# 03_-_CPU_POWER.net
KiCad netlist of a schematic drawn in Altium Designer
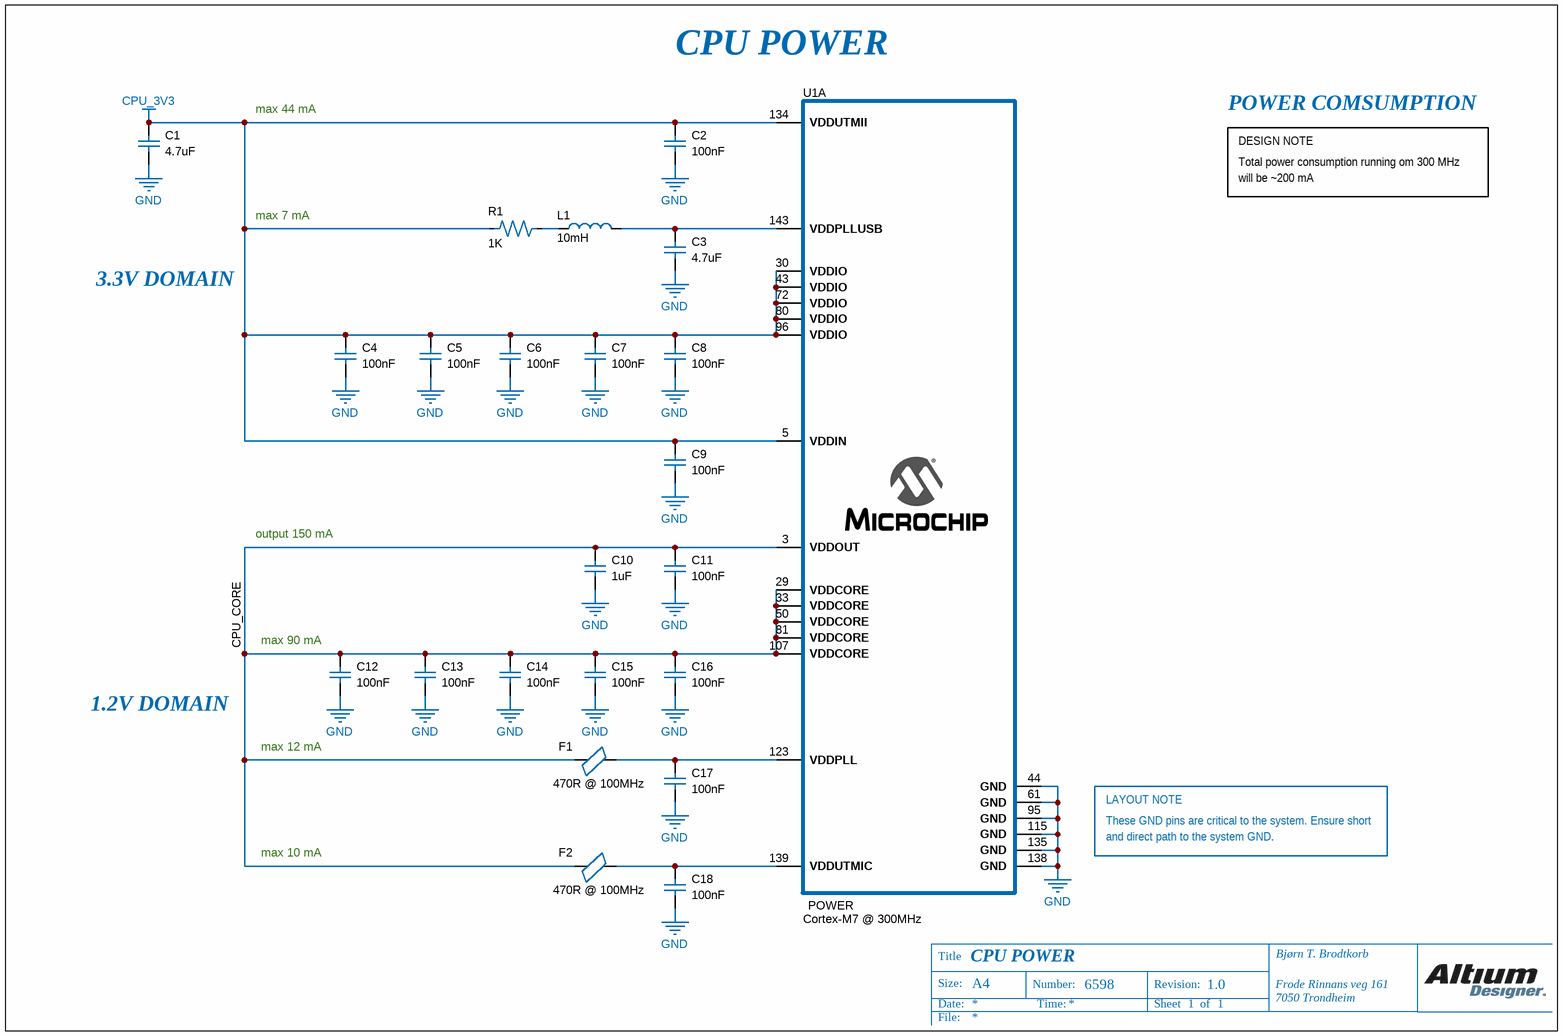
[diagram p0: [03] - CPU POWER.SchDoc]

(export (version "E")
  (design (tool "Eeschema 10.0.6"))
  (components
    (comp (ref "C1")
      (value "4.7uF")
      (footprint "C0603")
      (description "C0603")
      (fields (field (name "Comment") "02016D104KAT2A"))
      (libsource (lib "Passive components") (part "02016D104KAT2A"))
    )
    (comp (ref "C2")
      (value "100nF")
      (footprint "C0402")
      (description "C0402")
      (fields (field (name "Comment") "04023C103KAT2A"))
      (libsource (lib "Passive components") (part "04023C103KAT2A"))
    )
    (comp (ref "C3")
      (value "4.7uF")
      (footprint "C0402")
      (description "C0402")
      (fields (field (name "Comment") "04023C103KAT2A"))
      (libsource (lib "Passive components") (part "04023C103KAT2A"))
    )
    (comp (ref "C4")
      (value "100nF")
      (footprint "C0402")
      (description "C0402")
      (fields (field (name "Comment") "04023C103KAT2A"))
      (libsource (lib "Passive components") (part "04023C103KAT2A"))
    )
    (comp (ref "C5")
      (value "100nF")
      (footprint "C0402")
      (description "C0402")
      (fields (field (name "Comment") "04023C103KAT2A"))
      (libsource (lib "Passive components") (part "04023C103KAT2A"))
    )
    (comp (ref "C6")
      (value "100nF")
      (footprint "C0402")
      (description "C0402")
      (fields (field (name "Comment") "04023C103KAT2A"))
      (libsource (lib "Passive components") (part "04023C103KAT2A"))
    )
    (comp (ref "C7")
      (value "100nF")
      (footprint "C0402")
      (description "C0402")
      (fields (field (name "Comment") "04023C103KAT2A"))
      (libsource (lib "Passive components") (part "04023C103KAT2A"))
    )
    (comp (ref "C8")
      (value "100nF")
      (footprint "C0402")
      (description "C0402")
      (fields (field (name "Comment") "04023C103KAT2A"))
      (libsource (lib "Passive components") (part "04023C103KAT2A"))
    )
    (comp (ref "C9")
      (value "100nF")
      (footprint "C0402")
      (description "C0402")
      (fields (field (name "Comment") "04023C103KAT2A"))
      (libsource (lib "Passive components") (part "04023C103KAT2A"))
    )
    (comp (ref "C10")
      (value "1uF")
      (footprint "C0402")
      (description "C0402")
      (fields (field (name "Comment") "04023C103KAT2A"))
      (libsource (lib "Passive components") (part "04023C103KAT2A"))
    )
    (comp (ref "C11")
      (value "100nF")
      (footprint "C0402")
      (description "C0402")
      (fields (field (name "Comment") "04023C103KAT2A"))
      (libsource (lib "Passive components") (part "04023C103KAT2A"))
    )
    (comp (ref "C12")
      (value "100nF")
      (footprint "C0402")
      (description "C0402")
      (fields (field (name "Comment") "04023C103KAT2A"))
      (libsource (lib "Passive components") (part "04023C103KAT2A"))
    )
    (comp (ref "C13")
      (value "100nF")
      (footprint "C0402")
      (description "C0402")
      (fields (field (name "Comment") "04023C103KAT2A"))
      (libsource (lib "Passive components") (part "04023C103KAT2A"))
    )
    (comp (ref "C14")
      (value "100nF")
      (footprint "C0402")
      (description "C0402")
      (fields (field (name "Comment") "04023C103KAT2A"))
      (libsource (lib "Passive components") (part "04023C103KAT2A"))
    )
    (comp (ref "C15")
      (value "100nF")
      (footprint "C0402")
      (description "C0402")
      (fields (field (name "Comment") "04023C103KAT2A"))
      (libsource (lib "Passive components") (part "04023C103KAT2A"))
    )
    (comp (ref "C16")
      (value "100nF")
      (footprint "C0402")
      (description "C0402")
      (fields (field (name "Comment") "04023C103KAT2A"))
      (libsource (lib "Passive components") (part "04023C103KAT2A"))
    )
    (comp (ref "C17")
      (value "100nF")
      (footprint "C0402")
      (description "C0402")
      (fields (field (name "Comment") "04023C103KAT2A"))
      (libsource (lib "Passive components") (part "04023C103KAT2A"))
    )
    (comp (ref "C18")
      (value "100nF")
      (footprint "C0402")
      (description "C0402")
      (fields (field (name "Comment") "04023C103KAT2A"))
      (libsource (lib "Passive components") (part "04023C103KAT2A"))
    )
    (comp (ref "F1")
      (value "470R @ 100MHz")
      (footprint "Ferrite bead 0402")
      (description "Ferrite bead 0402")
      (fields (field (name "Comment") "BLM15AG102SN1D"))
      (libsource (lib "Passive components") (part "BLM15AG102SN1D"))
    )
    (comp (ref "F2")
      (value "470R @ 100MHz")
      (footprint "Ferrite bead 0402")
      (description "Ferrite bead 0402")
      (fields (field (name "Comment") "BLM15AG102SN1D"))
      (libsource (lib "Passive components") (part "BLM15AG102SN1D"))
    )
    (comp (ref "L1")
      (value "10mH")
      (footprint "Inductor 0603")
      (description "Inductor 0603")
      (fields (field (name "Comment") "MLZ1608A2R2WT"))
      (libsource (lib "Passive components") (part "MLZ1608A2R2WT"))
    )
    (comp (ref "R1")
      (value "1K")
      (footprint "R0402")
      (description "R0402")
      (fields (field (name "Comment") "CRCW04020000Z0ED"))
      (libsource (lib "Passive components") (part "CRCW04020000Z0ED"))
    )
    (comp (ref "U1")
      (value "Cortex-M7 @ 300MHz")
      (footprint "ATSAMS70Q21A-AN")
      (description "ATSAMS70Q21")
      (libsource (lib "Microcontrollers") (part "ATSAMS70Q21A-AN"))
    )
  )
  (nets
    (net (code "1") (name "/CPU_CORE") (class "Default")
      (node (ref "C10") (pin "2") (pinfunction "2_2") (pintype "passive"))
      (node (ref "C11") (pin "2") (pinfunction "2_2") (pintype "passive"))
      (node (ref "C12") (pin "2") (pinfunction "2_2") (pintype "passive"))
      (node (ref "C13") (pin "2") (pinfunction "2_2") (pintype "passive"))
      (node (ref "C14") (pin "2") (pinfunction "2_2") (pintype "passive"))
      (node (ref "C15") (pin "2") (pinfunction "2_2") (pintype "passive"))
      (node (ref "C16") (pin "2") (pinfunction "2_2") (pintype "passive"))
      (node (ref "F1") (pin "1") (pinfunction "1_1") (pintype "passive"))
      (node (ref "F2") (pin "1") (pinfunction "1_1") (pintype "passive"))
      (node (ref "U1") (pin "107") (pinfunction "VDDCORE_107") (pintype "power_in"))
      (node (ref "U1") (pin "29") (pinfunction "VDDCORE_29") (pintype "power_in"))
      (node (ref "U1") (pin "3") (pinfunction "VDDOUT_3") (pintype "power_in"))
      (node (ref "U1") (pin "33") (pinfunction "VDDCORE_33") (pintype "power_in"))
      (node (ref "U1") (pin "50") (pinfunction "VDDCORE_50") (pintype "power_in"))
      (node (ref "U1") (pin "81") (pinfunction "VDDCORE_81") (pintype "power_in"))
    )
    (net (code "2") (name "CPU_3V3") (class "Default")
      (node (ref "C1") (pin "1") (pinfunction "1_1") (pintype "passive"))
      (node (ref "C2") (pin "2") (pinfunction "2_2") (pintype "passive"))
      (node (ref "C4") (pin "2") (pinfunction "2_2") (pintype "passive"))
      (node (ref "C5") (pin "2") (pinfunction "2_2") (pintype "passive"))
      (node (ref "C6") (pin "2") (pinfunction "2_2") (pintype "passive"))
      (node (ref "C7") (pin "2") (pinfunction "2_2") (pintype "passive"))
      (node (ref "C8") (pin "2") (pinfunction "2_2") (pintype "passive"))
      (node (ref "C9") (pin "2") (pinfunction "2_2") (pintype "passive"))
      (node (ref "R1") (pin "1") (pinfunction "1_1") (pintype "passive"))
      (node (ref "U1") (pin "134") (pinfunction "VDDUTMII_134") (pintype "power_in"))
      (node (ref "U1") (pin "30") (pinfunction "VDDIO_30") (pintype "power_in"))
      (node (ref "U1") (pin "43") (pinfunction "VDDIO_43") (pintype "power_in"))
      (node (ref "U1") (pin "5") (pinfunction "VDDIN_5") (pintype "power_in"))
      (node (ref "U1") (pin "72") (pinfunction "VDDIO_72") (pintype "power_in"))
      (node (ref "U1") (pin "80") (pinfunction "VDDIO_80") (pintype "power_in"))
      (node (ref "U1") (pin "96") (pinfunction "VDDIO_96") (pintype "power_in"))
    )
    (net (code "3") (name "GND") (class "Default")
      (node (ref "C1") (pin "2") (pinfunction "2_2") (pintype "passive"))
      (node (ref "C10") (pin "1") (pinfunction "1_1") (pintype "passive"))
      (node (ref "C11") (pin "1") (pinfunction "1_1") (pintype "passive"))
      (node (ref "C12") (pin "1") (pinfunction "1_1") (pintype "passive"))
      (node (ref "C13") (pin "1") (pinfunction "1_1") (pintype "passive"))
      (node (ref "C14") (pin "1") (pinfunction "1_1") (pintype "passive"))
      (node (ref "C15") (pin "1") (pinfunction "1_1") (pintype "passive"))
      (node (ref "C16") (pin "1") (pinfunction "1_1") (pintype "passive"))
      (node (ref "C17") (pin "1") (pinfunction "1_1") (pintype "passive"))
      (node (ref "C18") (pin "1") (pinfunction "1_1") (pintype "passive"))
      (node (ref "C2") (pin "1") (pinfunction "1_1") (pintype "passive"))
      (node (ref "C3") (pin "1") (pinfunction "1_1") (pintype "passive"))
      (node (ref "C4") (pin "1") (pinfunction "1_1") (pintype "passive"))
      (node (ref "C5") (pin "1") (pinfunction "1_1") (pintype "passive"))
      (node (ref "C6") (pin "1") (pinfunction "1_1") (pintype "passive"))
      (node (ref "C7") (pin "1") (pinfunction "1_1") (pintype "passive"))
      (node (ref "C8") (pin "1") (pinfunction "1_1") (pintype "passive"))
      (node (ref "C9") (pin "1") (pinfunction "1_1") (pintype "passive"))
      (node (ref "U1") (pin "115") (pinfunction "GND_115") (pintype "power_in"))
      (node (ref "U1") (pin "135") (pinfunction "GND_135") (pintype "power_in"))
      (node (ref "U1") (pin "138") (pinfunction "GND_138") (pintype "power_in"))
      (node (ref "U1") (pin "44") (pinfunction "GND_44") (pintype "power_in"))
      (node (ref "U1") (pin "61") (pinfunction "GND_61") (pintype "power_in"))
      (node (ref "U1") (pin "95") (pinfunction "GND_95") (pintype "power_in"))
    )
    (net (code "4") (name "Net-(R1-3)") (class "Default")
      (node (ref "L1") (pin "1") (pinfunction "1_1") (pintype "passive"))
      (node (ref "R1") (pin "2") (pinfunction "3_2") (pintype "passive"))
    )
    (net (code "5") (name "Net-(U1A-VDDPLL)") (class "Default")
      (node (ref "C17") (pin "2") (pinfunction "2_2") (pintype "passive"))
      (node (ref "F1") (pin "2") (pinfunction "2_2") (pintype "passive"))
      (node (ref "U1") (pin "123") (pinfunction "VDDPLL_123") (pintype "power_in"))
    )
    (net (code "6") (name "Net-(U1A-VDDPLLUSB)") (class "Default")
      (node (ref "C3") (pin "2") (pinfunction "2_2") (pintype "passive"))
      (node (ref "L1") (pin "2") (pinfunction "2_2") (pintype "passive"))
      (node (ref "U1") (pin "143") (pinfunction "VDDPLLUSB_143") (pintype "power_in"))
    )
    (net (code "7") (name "Net-(U1A-VDDUTMIC)") (class "Default")
      (node (ref "C18") (pin "2") (pinfunction "2_2") (pintype "passive"))
      (node (ref "F2") (pin "2") (pinfunction "2_2") (pintype "passive"))
      (node (ref "U1") (pin "139") (pinfunction "VDDUTMIC_139") (pintype "power_in"))
    )
  )
)
